# DATN2022_MCU.net
KiCad netlist of a schematic drawn in Altium Designer
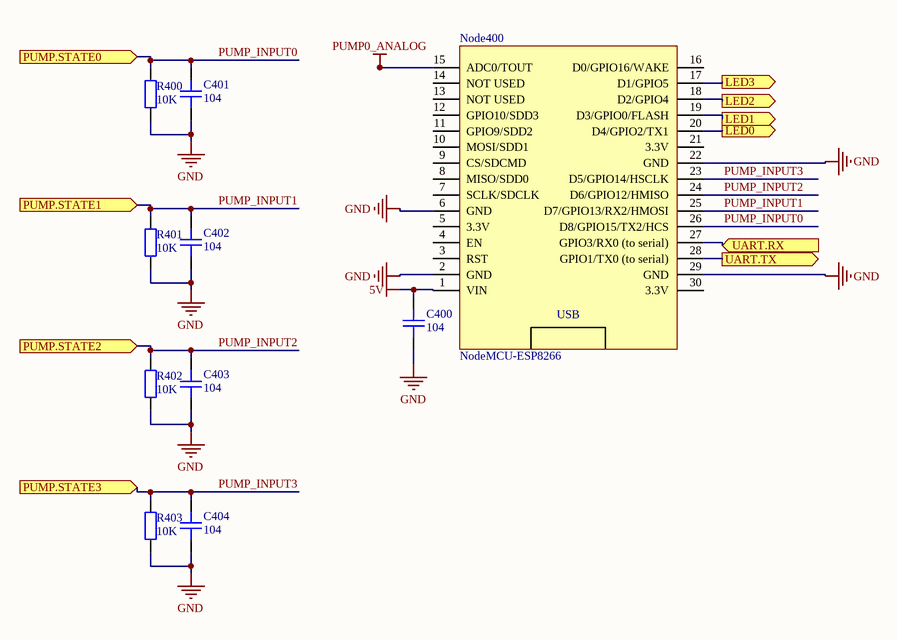
[diagram p0: DATN2022.MCU.SchDoc]

(export (version "E")
  (design (tool "Eeschema 10.0.6"))
  (components
    (comp (ref "C400")
      (value "104")
      (footprint "CAP_CERAMIC_0805(2012mm)")
      (description "Capacitor Ceramic SMD 0805(2012)")
      (fields (field (name "PUBLISHER") "Altium Limited"))
      (libsource (lib "01.Capacitor") (part "Cap Cer 0805 (2012)"))
    )
    (comp (ref "C401")
      (value "104")
      (footprint "CAP_CERAMIC_0805(2012mm)")
      (description "Capacitor Ceramic SMD 0805(2012)")
      (fields (field (name "PUBLISHER") "Altium Limited"))
      (libsource (lib "01.Capacitor") (part "Cap Cer 0805 (2012)"))
    )
    (comp (ref "C402")
      (value "104")
      (footprint "CAP_CERAMIC_0805(2012mm)")
      (description "Capacitor Ceramic SMD 0805(2012)")
      (fields (field (name "PUBLISHER") "Altium Limited"))
      (libsource (lib "01.Capacitor") (part "Cap Cer 0805 (2012)"))
    )
    (comp (ref "C403")
      (value "104")
      (footprint "CAP_CERAMIC_0805(2012mm)")
      (description "Capacitor Ceramic SMD 0805(2012)")
      (fields (field (name "PUBLISHER") "Altium Limited"))
      (libsource (lib "01.Capacitor") (part "Cap Cer 0805 (2012)"))
    )
    (comp (ref "C404")
      (value "104")
      (footprint "CAP_CERAMIC_0805(2012mm)")
      (description "Capacitor Ceramic SMD 0805(2012)")
      (fields (field (name "PUBLISHER") "Altium Limited"))
      (libsource (lib "01.Capacitor") (part "Cap Cer 0805 (2012)"))
    )
    (comp (ref "Node400")
      (value "NodeMCU-ESP8266")
      (footprint "NodeMCU_ESP8266")
      (libsource (lib "MCU") (part "NodeMCU_ESP8266"))
    )
    (comp (ref "R400")
      (value "10K")
      (footprint "RES_0805(2012)")
      (description "Resistor SMD 0805")
      (fields (field (name "PUBLISHER") "Altium Limited"))
      (libsource (lib "02.Resistor") (part "R0805"))
    )
    (comp (ref "R401")
      (value "10K")
      (footprint "RES_0805(2012)")
      (description "Resistor SMD 0805")
      (fields (field (name "PUBLISHER") "Altium Limited"))
      (libsource (lib "02.Resistor") (part "R0805"))
    )
    (comp (ref "R402")
      (value "10K")
      (footprint "RES_0805(2012)")
      (description "Resistor SMD 0805")
      (fields (field (name "PUBLISHER") "Altium Limited"))
      (libsource (lib "02.Resistor") (part "R0805"))
    )
    (comp (ref "R403")
      (value "10K")
      (footprint "RES_0805(2012)")
      (description "Resistor SMD 0805")
      (fields (field (name "PUBLISHER") "Altium Limited"))
      (libsource (lib "02.Resistor") (part "R0805"))
    )
  )
  (nets
    (net (code "1") (name "/LED0") (class "Default")
      (node (ref "Node400") (pin "20") (pinfunction "D4/GPIO2/TX1_20") (pintype "passive"))
    )
    (net (code "2") (name "/LED1") (class "Default")
      (node (ref "Node400") (pin "19") (pinfunction "D3/GPIO0/FLASH_19") (pintype "passive"))
    )
    (net (code "3") (name "/LED2") (class "Default")
      (node (ref "Node400") (pin "18") (pinfunction "D2/GPIO4_18") (pintype "passive"))
    )
    (net (code "4") (name "/LED3") (class "Default")
      (node (ref "Node400") (pin "17") (pinfunction "D1/GPIO5_17") (pintype "passive"))
    )
    (net (code "5") (name "/PUMP_INPUT0") (class "Default")
      (node (ref "C401") (pin "2") (pinfunction "2_2") (pintype "passive"))
      (node (ref "Node400") (pin "26") (pinfunction "D8/GPIO15/TX2/HCS_26") (pintype "passive"))
      (node (ref "R400") (pin "2") (pinfunction "2_2") (pintype "passive"))
    )
    (net (code "6") (name "/PUMP_INPUT1") (class "Default")
      (node (ref "C402") (pin "2") (pinfunction "2_2") (pintype "passive"))
      (node (ref "Node400") (pin "25") (pinfunction "D7/GPIO13/RX2/HMOSI_25") (pintype "passive"))
      (node (ref "R401") (pin "2") (pinfunction "2_2") (pintype "passive"))
    )
    (net (code "7") (name "/PUMP_INPUT2") (class "Default")
      (node (ref "C403") (pin "2") (pinfunction "2_2") (pintype "passive"))
      (node (ref "Node400") (pin "24") (pinfunction "D6/GPIO12/HMISO_24") (pintype "passive"))
      (node (ref "R402") (pin "2") (pinfunction "2_2") (pintype "passive"))
    )
    (net (code "8") (name "/PUMP_INPUT3") (class "Default")
      (node (ref "C404") (pin "2") (pinfunction "2_2") (pintype "passive"))
      (node (ref "Node400") (pin "23") (pinfunction "D5/GPIO14/HSCLK_23") (pintype "passive"))
      (node (ref "R403") (pin "2") (pinfunction "2_2") (pintype "passive"))
    )
    (net (code "9") (name "/UART.RX") (class "Default")
      (node (ref "Node400") (pin "27") (pinfunction "GPIO3/RX0_(to_serial)_27") (pintype "passive"))
    )
    (net (code "10") (name "/UART.TX") (class "Default")
      (node (ref "Node400") (pin "28") (pinfunction "GPIO1/TX0_(to_serial)_28") (pintype "passive"))
    )
    (net (code "11") (name "5V") (class "Default")
      (node (ref "C400") (pin "2") (pinfunction "2_2") (pintype "passive"))
      (node (ref "Node400") (pin "1") (pinfunction "VIN_1") (pintype "passive"))
    )
    (net (code "12") (name "GND") (class "Default")
      (node (ref "C400") (pin "1") (pinfunction "1_1") (pintype "passive"))
      (node (ref "C401") (pin "1") (pinfunction "1_1") (pintype "passive"))
      (node (ref "C402") (pin "1") (pinfunction "1_1") (pintype "passive"))
      (node (ref "C403") (pin "1") (pinfunction "1_1") (pintype "passive"))
      (node (ref "C404") (pin "1") (pinfunction "1_1") (pintype "passive"))
      (node (ref "Node400") (pin "2") (pinfunction "GND_2") (pintype "passive"))
      (node (ref "Node400") (pin "22") (pinfunction "GND_22") (pintype "passive"))
      (node (ref "Node400") (pin "29") (pinfunction "GND_29") (pintype "passive"))
      (node (ref "Node400") (pin "6") (pinfunction "GND_6") (pintype "passive"))
      (node (ref "R400") (pin "1") (pinfunction "1_1") (pintype "passive"))
      (node (ref "R401") (pin "1") (pinfunction "1_1") (pintype "passive"))
      (node (ref "R402") (pin "1") (pinfunction "1_1") (pintype "passive"))
      (node (ref "R403") (pin "1") (pinfunction "1_1") (pintype "passive"))
    )
    (net (code "13") (name "PUMP0_ANALOG") (class "Default")
      (node (ref "Node400") (pin "15") (pinfunction "ADC0/TOUT_15") (pintype "passive"))
    )
    (net (code "14") (name "unconnected-(Node400-3.3V-Pad5)") (class "Default")
      (node (ref "Node400") (pin "5") (pinfunction "3.3V_5") (pintype "passive"))
    )
    (net (code "15") (name "unconnected-(Node400-3.3V-Pad21)") (class "Default")
      (node (ref "Node400") (pin "21") (pinfunction "3.3V_21") (pintype "passive"))
    )
    (net (code "16") (name "unconnected-(Node400-3.3V-Pad30)") (class "Default")
      (node (ref "Node400") (pin "30") (pinfunction "3.3V_30") (pintype "passive"))
    )
    (net (code "17") (name "unconnected-(Node400-CS{slash}SDCMD-Pad9)") (class "Default")
      (node (ref "Node400") (pin "9") (pinfunction "CS/SDCMD_9") (pintype "passive"))
    )
    (net (code "18") (name "unconnected-(Node400-D0{slash}GPIO16{slash}WAKE-Pad16)") (class "Default")
      (node (ref "Node400") (pin "16") (pinfunction "D0/GPIO16/WAKE_16") (pintype "passive"))
    )
    (net (code "19") (name "unconnected-(Node400-EN-Pad4)") (class "Default")
      (node (ref "Node400") (pin "4") (pinfunction "EN_4") (pintype "passive"))
    )
    (net (code "20") (name "unconnected-(Node400-GPIO9{slash}SDD2-Pad11)") (class "Default")
      (node (ref "Node400") (pin "11") (pinfunction "GPIO9/SDD2_11") (pintype "passive"))
    )
    (net (code "21") (name "unconnected-(Node400-GPIO10{slash}SDD3-Pad12)") (class "Default")
      (node (ref "Node400") (pin "12") (pinfunction "GPIO10/SDD3_12") (pintype "passive"))
    )
    (net (code "22") (name "unconnected-(Node400-MISO{slash}SDD0-Pad8)") (class "Default")
      (node (ref "Node400") (pin "8") (pinfunction "MISO/SDD0_8") (pintype "passive"))
    )
    (net (code "23") (name "unconnected-(Node400-MOSI{slash}SDD1-Pad10)") (class "Default")
      (node (ref "Node400") (pin "10") (pinfunction "MOSI/SDD1_10") (pintype "passive"))
    )
    (net (code "24") (name "unconnected-(Node400-NOT_USED-Pad13)") (class "Default")
      (node (ref "Node400") (pin "13") (pinfunction "NOT_USED_13") (pintype "passive"))
    )
    (net (code "25") (name "unconnected-(Node400-NOT_USED-Pad14)") (class "Default")
      (node (ref "Node400") (pin "14") (pinfunction "NOT_USED_14") (pintype "passive"))
    )
    (net (code "26") (name "unconnected-(Node400-RST-Pad3)") (class "Default")
      (node (ref "Node400") (pin "3") (pinfunction "RST_3") (pintype "passive"))
    )
    (net (code "27") (name "unconnected-(Node400-SCLK{slash}SDCLK-Pad7)") (class "Default")
      (node (ref "Node400") (pin "7") (pinfunction "SCLK/SDCLK_7") (pintype "passive"))
    )
  )
)
